# board.net
KiCad netlist of a schematic drawn in EAGLE
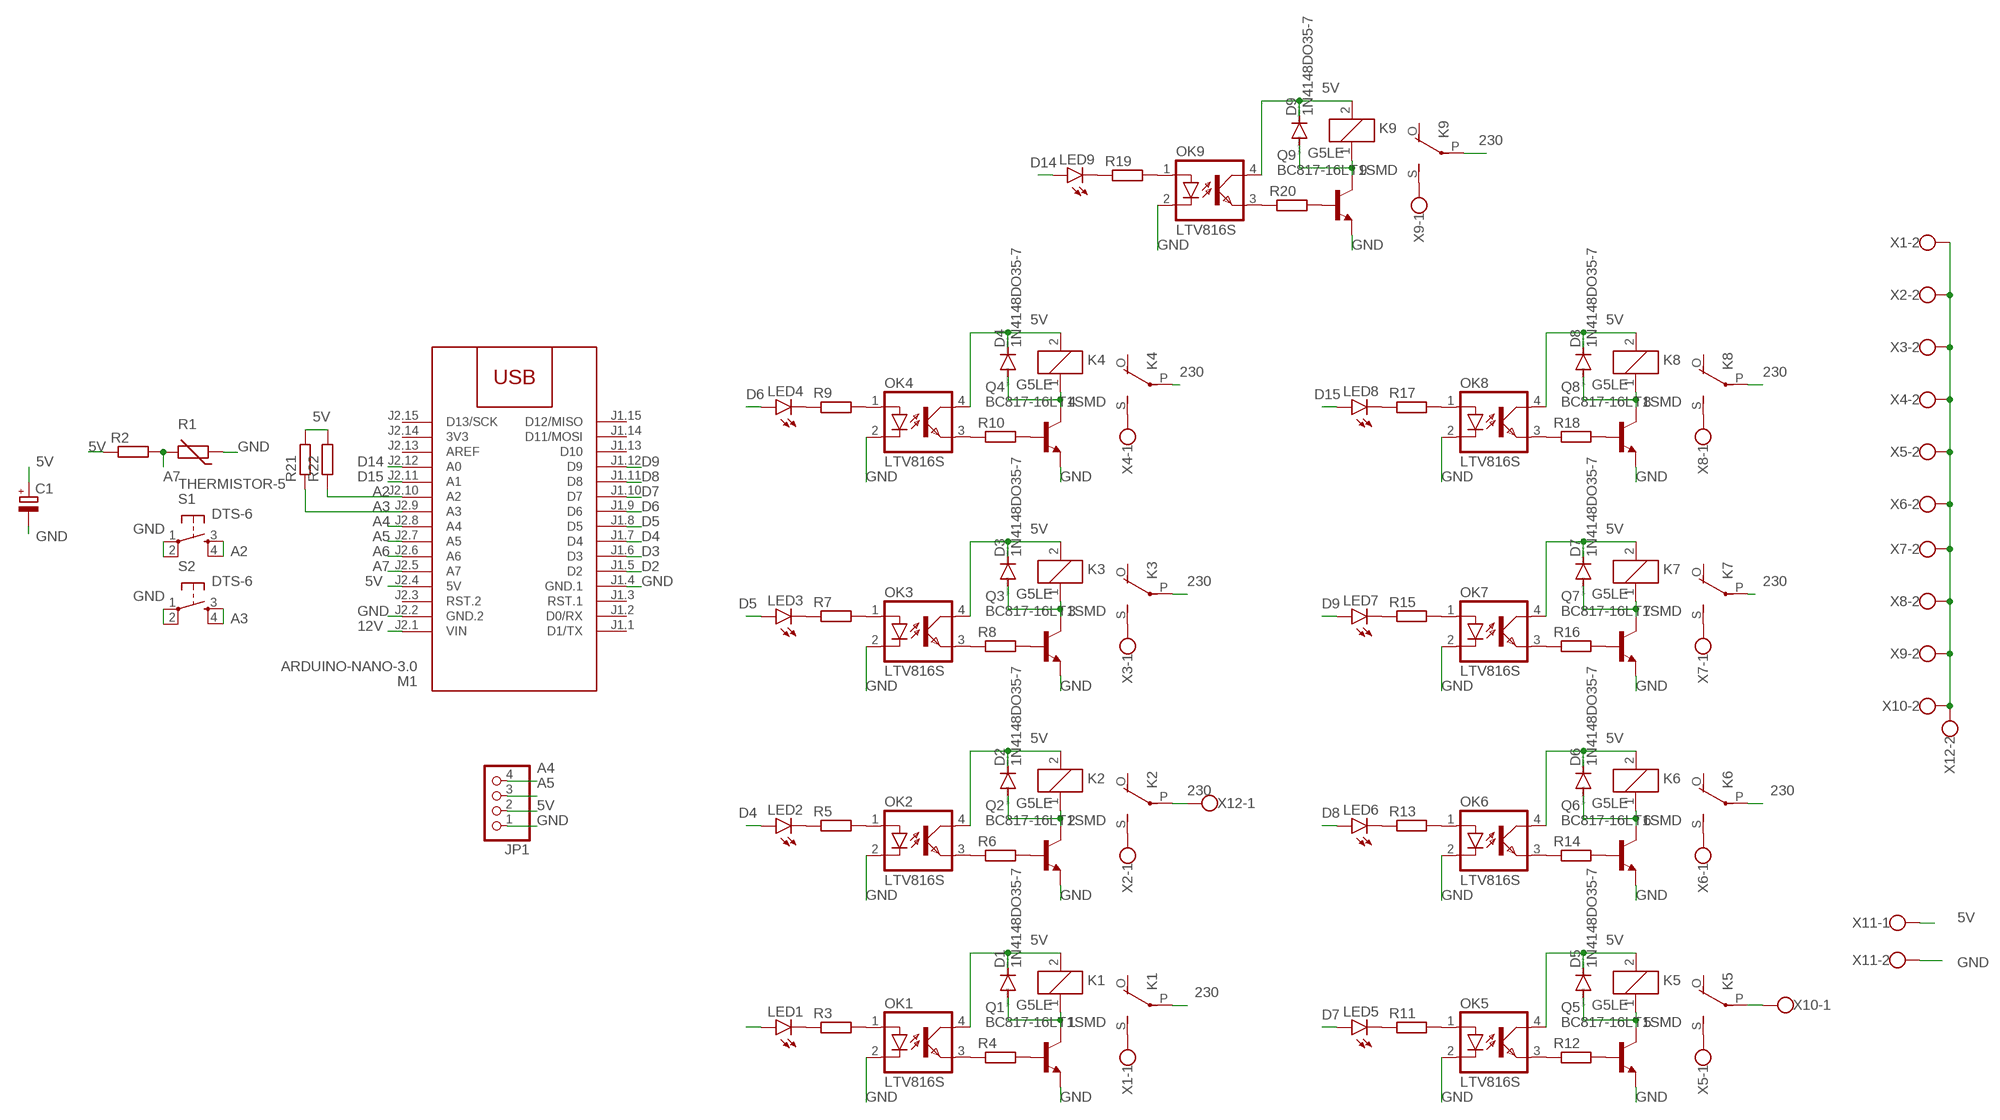
[diagram p0: schematic, sheet 1]

(export (version "E")
  (design (tool "Eeschema 10.0.6"))
  (components
    (comp (ref "C1")
      (value "CPOL-EUB45181A")
      (footprint "eagle-import:B45181A")
      (libsource (lib "eagle-import") (part "CPOL-EUB45181A"))
    )
    (comp (ref "D1")
      (value "1N4148DO35-7")
      (footprint "eagle-import:DO35-7")
      (libsource (lib "eagle-import") (part "1N4148DO35-7"))
    )
    (comp (ref "D2")
      (value "1N4148DO35-7")
      (footprint "eagle-import:DO35-7")
      (libsource (lib "eagle-import") (part "1N4148DO35-7"))
    )
    (comp (ref "D3")
      (value "1N4148DO35-7")
      (footprint "eagle-import:DO35-7")
      (libsource (lib "eagle-import") (part "1N4148DO35-7"))
    )
    (comp (ref "D4")
      (value "1N4148DO35-7")
      (footprint "eagle-import:DO35-7")
      (libsource (lib "eagle-import") (part "1N4148DO35-7"))
    )
    (comp (ref "D5")
      (value "1N4148DO35-7")
      (footprint "eagle-import:DO35-7")
      (libsource (lib "eagle-import") (part "1N4148DO35-7"))
    )
    (comp (ref "D6")
      (value "1N4148DO35-7")
      (footprint "eagle-import:DO35-7")
      (libsource (lib "eagle-import") (part "1N4148DO35-7"))
    )
    (comp (ref "D7")
      (value "1N4148DO35-7")
      (footprint "eagle-import:DO35-7")
      (libsource (lib "eagle-import") (part "1N4148DO35-7"))
    )
    (comp (ref "D8")
      (value "1N4148DO35-7")
      (footprint "eagle-import:DO35-7")
      (libsource (lib "eagle-import") (part "1N4148DO35-7"))
    )
    (comp (ref "D9")
      (value "1N4148DO35-7")
      (footprint "eagle-import:DO35-7")
      (libsource (lib "eagle-import") (part "1N4148DO35-7"))
    )
    (comp (ref "JP1")
      (value "PINHD-1X4")
      (footprint "eagle-import:1X04")
      (libsource (lib "eagle-import") (part "PINHD-1X4"))
    )
    (comp (ref "K1")
      (value "G5LE")
      (footprint "eagle-import:G5LE")
      (libsource (lib "eagle-import") (part "G5LE"))
    )
    (comp (ref "K2")
      (value "G5LE")
      (footprint "eagle-import:G5LE")
      (libsource (lib "eagle-import") (part "G5LE"))
    )
    (comp (ref "K3")
      (value "G5LE")
      (footprint "eagle-import:G5LE")
      (libsource (lib "eagle-import") (part "G5LE"))
    )
    (comp (ref "K4")
      (value "G5LE")
      (footprint "eagle-import:G5LE")
      (libsource (lib "eagle-import") (part "G5LE"))
    )
    (comp (ref "K5")
      (value "G5LE")
      (footprint "eagle-import:G5LE")
      (libsource (lib "eagle-import") (part "G5LE"))
    )
    (comp (ref "K6")
      (value "G5LE")
      (footprint "eagle-import:G5LE")
      (libsource (lib "eagle-import") (part "G5LE"))
    )
    (comp (ref "K7")
      (value "G5LE")
      (footprint "eagle-import:G5LE")
      (libsource (lib "eagle-import") (part "G5LE"))
    )
    (comp (ref "K8")
      (value "G5LE")
      (footprint "eagle-import:G5LE")
      (libsource (lib "eagle-import") (part "G5LE"))
    )
    (comp (ref "K9")
      (value "G5LE")
      (footprint "eagle-import:G5LE")
      (libsource (lib "eagle-import") (part "G5LE"))
    )
    (comp (ref "LED1")
      (value "LED3MM")
      (footprint "eagle-import:LED3MM")
      (libsource (lib "eagle-import") (part "LED3MM"))
    )
    (comp (ref "LED2")
      (value "LED3MM")
      (footprint "eagle-import:LED3MM")
      (libsource (lib "eagle-import") (part "LED3MM"))
    )
    (comp (ref "LED3")
      (value "LED3MM")
      (footprint "eagle-import:LED3MM")
      (libsource (lib "eagle-import") (part "LED3MM"))
    )
    (comp (ref "LED4")
      (value "LED3MM")
      (footprint "eagle-import:LED3MM")
      (libsource (lib "eagle-import") (part "LED3MM"))
    )
    (comp (ref "LED5")
      (value "LED3MM")
      (footprint "eagle-import:LED3MM")
      (libsource (lib "eagle-import") (part "LED3MM"))
    )
    (comp (ref "LED6")
      (value "LED3MM")
      (footprint "eagle-import:LED3MM")
      (libsource (lib "eagle-import") (part "LED3MM"))
    )
    (comp (ref "LED7")
      (value "LED3MM")
      (footprint "eagle-import:LED3MM")
      (libsource (lib "eagle-import") (part "LED3MM"))
    )
    (comp (ref "LED8")
      (value "LED3MM")
      (footprint "eagle-import:LED3MM")
      (libsource (lib "eagle-import") (part "LED3MM"))
    )
    (comp (ref "LED9")
      (value "LED3MM")
      (footprint "eagle-import:LED3MM")
      (libsource (lib "eagle-import") (part "LED3MM"))
    )
    (comp (ref "M1")
      (value "ARDUINO-NANO-3.0")
      (footprint "eagle-import:ARDUINO-NANO-3.0")
      (libsource (lib "eagle-import") (part "ARDUINO-NANO-3.0"))
    )
    (comp (ref "OK1")
      (value "LTV816S")
      (footprint "eagle-import:DIL4-SMD")
      (libsource (lib "eagle-import") (part "LTV816S"))
    )
    (comp (ref "OK2")
      (value "LTV816S")
      (footprint "eagle-import:DIL4-SMD")
      (libsource (lib "eagle-import") (part "LTV816S"))
    )
    (comp (ref "OK3")
      (value "LTV816S")
      (footprint "eagle-import:DIL4-SMD")
      (libsource (lib "eagle-import") (part "LTV816S"))
    )
    (comp (ref "OK4")
      (value "LTV816S")
      (footprint "eagle-import:DIL4-SMD")
      (libsource (lib "eagle-import") (part "LTV816S"))
    )
    (comp (ref "OK5")
      (value "LTV816S")
      (footprint "eagle-import:DIL4-SMD")
      (libsource (lib "eagle-import") (part "LTV816S"))
    )
    (comp (ref "OK6")
      (value "LTV816S")
      (footprint "eagle-import:DIL4-SMD")
      (libsource (lib "eagle-import") (part "LTV816S"))
    )
    (comp (ref "OK7")
      (value "LTV816S")
      (footprint "eagle-import:DIL4-SMD")
      (libsource (lib "eagle-import") (part "LTV816S"))
    )
    (comp (ref "OK8")
      (value "LTV816S")
      (footprint "eagle-import:DIL4-SMD")
      (libsource (lib "eagle-import") (part "LTV816S"))
    )
    (comp (ref "OK9")
      (value "LTV816S")
      (footprint "eagle-import:DIL4-SMD")
      (libsource (lib "eagle-import") (part "LTV816S"))
    )
    (comp (ref "Q1")
      (value "BC817-16LT1SMD")
      (footprint "eagle-import:SOT23-BEC")
      (libsource (lib "eagle-import") (part "BC817SMD-16LT1"))
    )
    (comp (ref "Q2")
      (value "BC817-16LT1SMD")
      (footprint "eagle-import:SOT23-BEC")
      (libsource (lib "eagle-import") (part "BC817SMD-16LT1"))
    )
    (comp (ref "Q3")
      (value "BC817-16LT1SMD")
      (footprint "eagle-import:SOT23-BEC")
      (libsource (lib "eagle-import") (part "BC817SMD-16LT1"))
    )
    (comp (ref "Q4")
      (value "BC817-16LT1SMD")
      (footprint "eagle-import:SOT23-BEC")
      (libsource (lib "eagle-import") (part "BC817SMD-16LT1"))
    )
    (comp (ref "Q5")
      (value "BC817-16LT1SMD")
      (footprint "eagle-import:SOT23-BEC")
      (libsource (lib "eagle-import") (part "BC817SMD-16LT1"))
    )
    (comp (ref "Q6")
      (value "BC817-16LT1SMD")
      (footprint "eagle-import:SOT23-BEC")
      (libsource (lib "eagle-import") (part "BC817SMD-16LT1"))
    )
    (comp (ref "Q7")
      (value "BC817-16LT1SMD")
      (footprint "eagle-import:SOT23-BEC")
      (libsource (lib "eagle-import") (part "BC817SMD-16LT1"))
    )
    (comp (ref "Q8")
      (value "BC817-16LT1SMD")
      (footprint "eagle-import:SOT23-BEC")
      (libsource (lib "eagle-import") (part "BC817SMD-16LT1"))
    )
    (comp (ref "Q9")
      (value "BC817-16LT1SMD")
      (footprint "eagle-import:SOT23-BEC")
      (libsource (lib "eagle-import") (part "BC817SMD-16LT1"))
    )
    (comp (ref "R1")
      (value "THERMISTOR-5")
      (footprint "eagle-import:R-5")
      (libsource (lib "eagle-import") (part "THERMISTOR-5"))
    )
    (comp (ref "R2")
      (value "R-EU_0207/10")
      (footprint "eagle-import:0207_10")
      (libsource (lib "eagle-import") (part "R-EU_0207/10"))
    )
    (comp (ref "R3")
      (value "R-EU_R1206")
      (footprint "eagle-import:R1206")
      (libsource (lib "eagle-import") (part "R-EU_R1206"))
    )
    (comp (ref "R4")
      (value "R-EU_R1206")
      (footprint "eagle-import:R1206")
      (libsource (lib "eagle-import") (part "R-EU_R1206"))
    )
    (comp (ref "R5")
      (value "R-EU_R1206")
      (footprint "eagle-import:R1206")
      (libsource (lib "eagle-import") (part "R-EU_R1206"))
    )
    (comp (ref "R6")
      (value "R-EU_R1206")
      (footprint "eagle-import:R1206")
      (libsource (lib "eagle-import") (part "R-EU_R1206"))
    )
    (comp (ref "R7")
      (value "R-EU_R1206")
      (footprint "eagle-import:R1206")
      (libsource (lib "eagle-import") (part "R-EU_R1206"))
    )
    (comp (ref "R8")
      (value "R-EU_R1206")
      (footprint "eagle-import:R1206")
      (libsource (lib "eagle-import") (part "R-EU_R1206"))
    )
    (comp (ref "R9")
      (value "R-EU_R1206")
      (footprint "eagle-import:R1206")
      (libsource (lib "eagle-import") (part "R-EU_R1206"))
    )
    (comp (ref "R10")
      (value "R-EU_R1206")
      (footprint "eagle-import:R1206")
      (libsource (lib "eagle-import") (part "R-EU_R1206"))
    )
    (comp (ref "R11")
      (value "R-EU_R1206")
      (footprint "eagle-import:R1206")
      (libsource (lib "eagle-import") (part "R-EU_R1206"))
    )
    (comp (ref "R12")
      (value "R-EU_R1206")
      (footprint "eagle-import:R1206")
      (libsource (lib "eagle-import") (part "R-EU_R1206"))
    )
    (comp (ref "R13")
      (value "R-EU_R1206")
      (footprint "eagle-import:R1206")
      (libsource (lib "eagle-import") (part "R-EU_R1206"))
    )
    (comp (ref "R14")
      (value "R-EU_R1206")
      (footprint "eagle-import:R1206")
      (libsource (lib "eagle-import") (part "R-EU_R1206"))
    )
    (comp (ref "R15")
      (value "R-EU_R1206")
      (footprint "eagle-import:R1206")
      (libsource (lib "eagle-import") (part "R-EU_R1206"))
    )
    (comp (ref "R16")
      (value "R-EU_R1206")
      (footprint "eagle-import:R1206")
      (libsource (lib "eagle-import") (part "R-EU_R1206"))
    )
    (comp (ref "R17")
      (value "R-EU_R1206")
      (footprint "eagle-import:R1206")
      (libsource (lib "eagle-import") (part "R-EU_R1206"))
    )
    (comp (ref "R18")
      (value "R-EU_R1206")
      (footprint "eagle-import:R1206")
      (libsource (lib "eagle-import") (part "R-EU_R1206"))
    )
    (comp (ref "R19")
      (value "R-EU_R1206")
      (footprint "eagle-import:R1206")
      (libsource (lib "eagle-import") (part "R-EU_R1206"))
    )
    (comp (ref "R20")
      (value "R-EU_R1206")
      (footprint "eagle-import:R1206")
      (libsource (lib "eagle-import") (part "R-EU_R1206"))
    )
    (comp (ref "R21")
      (value "R-EU_0207/10")
      (footprint "eagle-import:0207_10")
      (libsource (lib "eagle-import") (part "R-EU_0207/10"))
    )
    (comp (ref "R22")
      (value "R-EU_0207/10")
      (footprint "eagle-import:0207_10")
      (libsource (lib "eagle-import") (part "R-EU_0207/10"))
    )
    (comp (ref "S1")
      (value "DTS-6")
      (footprint "eagle-import:DTS-6")
      (libsource (lib "eagle-import") (part "DTS-6"))
    )
    (comp (ref "S2")
      (value "DTS-6")
      (footprint "eagle-import:DTS-6")
      (libsource (lib "eagle-import") (part "DTS-6"))
    )
    (comp (ref "X1")
      (value "W237-102")
      (footprint "eagle-import:W237-102")
      (fields (field (name "MPN") "237-102"))
      (libsource (lib "eagle-import") (part "W237-102"))
    )
    (comp (ref "X2")
      (value "W237-102")
      (footprint "eagle-import:W237-102")
      (fields (field (name "MPN") "237-102"))
      (libsource (lib "eagle-import") (part "W237-102"))
    )
    (comp (ref "X3")
      (value "W237-102")
      (footprint "eagle-import:W237-102")
      (fields (field (name "MPN") "237-102"))
      (libsource (lib "eagle-import") (part "W237-102"))
    )
    (comp (ref "X4")
      (value "W237-102")
      (footprint "eagle-import:W237-102")
      (fields (field (name "MPN") "237-102"))
      (libsource (lib "eagle-import") (part "W237-102"))
    )
    (comp (ref "X5")
      (value "W237-102")
      (footprint "eagle-import:W237-102")
      (fields (field (name "MPN") "237-102"))
      (libsource (lib "eagle-import") (part "W237-102"))
    )
    (comp (ref "X6")
      (value "W237-102")
      (footprint "eagle-import:W237-102")
      (fields (field (name "MPN") "237-102"))
      (libsource (lib "eagle-import") (part "W237-102"))
    )
    (comp (ref "X7")
      (value "W237-102")
      (footprint "eagle-import:W237-102")
      (fields (field (name "MPN") "237-102"))
      (libsource (lib "eagle-import") (part "W237-102"))
    )
    (comp (ref "X8")
      (value "W237-102")
      (footprint "eagle-import:W237-102")
      (fields (field (name "MPN") "237-102"))
      (libsource (lib "eagle-import") (part "W237-102"))
    )
    (comp (ref "X9")
      (value "W237-102")
      (footprint "eagle-import:W237-102")
      (fields (field (name "MPN") "237-102"))
      (libsource (lib "eagle-import") (part "W237-102"))
    )
    (comp (ref "X10")
      (value "W237-102")
      (footprint "eagle-import:W237-102")
      (fields (field (name "MPN") "237-102"))
      (libsource (lib "eagle-import") (part "W237-102"))
    )
    (comp (ref "X11")
      (value "W237-102")
      (footprint "eagle-import:W237-102")
      (fields (field (name "MPN") "237-102"))
      (libsource (lib "eagle-import") (part "W237-102"))
    )
    (comp (ref "X12")
      (value "W237-102")
      (footprint "eagle-import:W237-102")
      (fields (field (name "MPN") "237-102"))
      (libsource (lib "eagle-import") (part "W237-102"))
    )
  )
  (nets
    (net (code "1") (name "/1") (class "Default")
      (node (ref "D1") (pin "A") (pinfunction "A_A") (pintype "passive"))
      (node (ref "K1") (pin "1") (pinfunction "1_1") (pintype "passive"))
      (node (ref "Q1") (pin "C") (pinfunction "C_C") (pintype "passive"))
    )
    (net (code "2") (name "/2") (class "Default")
      (node (ref "D2") (pin "A") (pinfunction "A_A") (pintype "passive"))
      (node (ref "K2") (pin "1") (pinfunction "1_1") (pintype "passive"))
      (node (ref "Q2") (pin "C") (pinfunction "C_C") (pintype "passive"))
    )
    (net (code "3") (name "/3") (class "Default")
      (node (ref "D3") (pin "A") (pinfunction "A_A") (pintype "passive"))
      (node (ref "K3") (pin "1") (pinfunction "1_1") (pintype "passive"))
      (node (ref "Q3") (pin "C") (pinfunction "C_C") (pintype "passive"))
    )
    (net (code "4") (name "/3V3") (class "Default")
      (node (ref "M1") (pin "J2.14") (pinfunction "3V3_J2.14") (pintype "power_in"))
    )
    (net (code "5") (name "/4") (class "Default")
      (node (ref "D4") (pin "A") (pinfunction "A_A") (pintype "passive"))
      (node (ref "K4") (pin "1") (pinfunction "1_1") (pintype "passive"))
      (node (ref "Q4") (pin "C") (pinfunction "C_C") (pintype "passive"))
    )
    (net (code "6") (name "/5") (class "Default")
      (node (ref "D5") (pin "A") (pinfunction "A_A") (pintype "passive"))
      (node (ref "K5") (pin "1") (pinfunction "1_1") (pintype "passive"))
      (node (ref "Q5") (pin "C") (pinfunction "C_C") (pintype "passive"))
    )
    (net (code "7") (name "/5V") (class "Default")
      (node (ref "C1") (pin "+") (pinfunction "+_+") (pintype "passive"))
      (node (ref "D1") (pin "C") (pinfunction "C_C") (pintype "passive"))
      (node (ref "D2") (pin "C") (pinfunction "C_C") (pintype "passive"))
      (node (ref "D3") (pin "C") (pinfunction "C_C") (pintype "passive"))
      (node (ref "D4") (pin "C") (pinfunction "C_C") (pintype "passive"))
      (node (ref "D5") (pin "C") (pinfunction "C_C") (pintype "passive"))
      (node (ref "D6") (pin "C") (pinfunction "C_C") (pintype "passive"))
      (node (ref "D7") (pin "C") (pinfunction "C_C") (pintype "passive"))
      (node (ref "D8") (pin "C") (pinfunction "C_C") (pintype "passive"))
      (node (ref "D9") (pin "C") (pinfunction "C_C") (pintype "passive"))
      (node (ref "JP1") (pin "2") (pinfunction "2_2") (pintype "passive"))
      (node (ref "K1") (pin "2") (pinfunction "2_2") (pintype "passive"))
      (node (ref "K2") (pin "2") (pinfunction "2_2") (pintype "passive"))
      (node (ref "K3") (pin "2") (pinfunction "2_2") (pintype "passive"))
      (node (ref "K4") (pin "2") (pinfunction "2_2") (pintype "passive"))
      (node (ref "K5") (pin "2") (pinfunction "2_2") (pintype "passive"))
      (node (ref "K6") (pin "2") (pinfunction "2_2") (pintype "passive"))
      (node (ref "K7") (pin "2") (pinfunction "2_2") (pintype "passive"))
      (node (ref "K8") (pin "2") (pinfunction "2_2") (pintype "passive"))
      (node (ref "K9") (pin "2") (pinfunction "2_2") (pintype "passive"))
      (node (ref "M1") (pin "J2.4") (pinfunction "5V_J2.4") (pintype "power_in"))
      (node (ref "OK1") (pin "4") (pinfunction "COL_4") (pintype "passive"))
      (node (ref "OK2") (pin "4") (pinfunction "COL_4") (pintype "passive"))
      (node (ref "OK3") (pin "4") (pinfunction "COL_4") (pintype "passive"))
      (node (ref "OK4") (pin "4") (pinfunction "COL_4") (pintype "passive"))
      (node (ref "OK5") (pin "4") (pinfunction "COL_4") (pintype "passive"))
      (node (ref "OK6") (pin "4") (pinfunction "COL_4") (pintype "passive"))
      (node (ref "OK7") (pin "4") (pinfunction "COL_4") (pintype "passive"))
      (node (ref "OK8") (pin "4") (pinfunction "COL_4") (pintype "passive"))
      (node (ref "OK9") (pin "4") (pinfunction "COL_4") (pintype "passive"))
      (node (ref "R2") (pin "1") (pinfunction "1_1") (pintype "passive"))
      (node (ref "R21") (pin "2") (pinfunction "2_2") (pintype "passive"))
      (node (ref "R22") (pin "2") (pinfunction "2_2") (pintype "passive"))
      (node (ref "X11") (pin "1") (pinfunction "KL_1") (pintype "passive"))
    )
    (net (code "8") (name "/6") (class "Default")
      (node (ref "D6") (pin "A") (pinfunction "A_A") (pintype "passive"))
      (node (ref "K6") (pin "1") (pinfunction "1_1") (pintype "passive"))
      (node (ref "Q6") (pin "C") (pinfunction "C_C") (pintype "passive"))
    )
    (net (code "9") (name "/7") (class "Default")
      (node (ref "D7") (pin "A") (pinfunction "A_A") (pintype "passive"))
      (node (ref "K7") (pin "1") (pinfunction "1_1") (pintype "passive"))
      (node (ref "Q7") (pin "C") (pinfunction "C_C") (pintype "passive"))
    )
    (net (code "10") (name "/8") (class "Default")
      (node (ref "D8") (pin "A") (pinfunction "A_A") (pintype "passive"))
      (node (ref "K8") (pin "1") (pinfunction "1_1") (pintype "passive"))
      (node (ref "Q8") (pin "C") (pinfunction "C_C") (pintype "passive"))
    )
    (net (code "11") (name "/9") (class "Default")
      (node (ref "D9") (pin "A") (pinfunction "A_A") (pintype "passive"))
      (node (ref "K9") (pin "1") (pinfunction "1_1") (pintype "passive"))
      (node (ref "Q9") (pin "C") (pinfunction "C_C") (pintype "passive"))
    )
    (net (code "12") (name "/12V") (class "Default")
      (node (ref "M1") (pin "J2.1") (pinfunction "VIN_J2.1") (pintype "power_in"))
    )
    (net (code "13") (name "/230") (class "Default")
      (node (ref "K1") (pin "P") (pinfunction "P_P") (pintype "passive"))
      (node (ref "K2") (pin "P") (pinfunction "P_P") (pintype "passive"))
      (node (ref "K3") (pin "P") (pinfunction "P_P") (pintype "passive"))
      (node (ref "K4") (pin "P") (pinfunction "P_P") (pintype "passive"))
      (node (ref "K5") (pin "P") (pinfunction "P_P") (pintype "passive"))
      (node (ref "K6") (pin "P") (pinfunction "P_P") (pintype "passive"))
      (node (ref "K7") (pin "P") (pinfunction "P_P") (pintype "passive"))
      (node (ref "K8") (pin "P") (pinfunction "P_P") (pintype "passive"))
      (node (ref "K9") (pin "P") (pinfunction "P_P") (pintype "passive"))
      (node (ref "X10") (pin "1") (pinfunction "KL_1") (pintype "passive"))
      (node (ref "X12") (pin "1") (pinfunction "KL_1") (pintype "passive"))
    )
    (net (code "14") (name "/A2") (class "Default")
      (node (ref "M1") (pin "J2.10") (pinfunction "A2_J2.10") (pintype "bidirectional"))
      (node (ref "R22") (pin "1") (pinfunction "1_1") (pintype "passive"))
      (node (ref "S1") (pin "3") (pinfunction "3_3") (pintype "passive"))
      (node (ref "S1") (pin "4") (pinfunction "4_4") (pintype "passive"))
    )
    (net (code "15") (name "/A3") (class "Default")
      (node (ref "M1") (pin "J2.9") (pinfunction "A3_J2.9") (pintype "bidirectional"))
      (node (ref "R21") (pin "1") (pinfunction "1_1") (pintype "passive"))
      (node (ref "S2") (pin "3") (pinfunction "3_3") (pintype "passive"))
      (node (ref "S2") (pin "4") (pinfunction "4_4") (pintype "passive"))
    )
    (net (code "16") (name "/A4") (class "Default")
      (node (ref "JP1") (pin "4") (pinfunction "4_4") (pintype "passive"))
      (node (ref "M1") (pin "J2.8") (pinfunction "A4_J2.8") (pintype "bidirectional"))
    )
    (net (code "17") (name "/A5") (class "Default")
      (node (ref "JP1") (pin "3") (pinfunction "3_3") (pintype "passive"))
      (node (ref "M1") (pin "J2.7") (pinfunction "A5_J2.7") (pintype "bidirectional"))
    )
    (net (code "18") (name "/A6") (class "Default")
      (node (ref "M1") (pin "J2.6") (pinfunction "A6_J2.6") (pintype "bidirectional"))
    )
    (net (code "19") (name "/A7") (class "Default")
      (node (ref "M1") (pin "J2.5") (pinfunction "A7_J2.5") (pintype "bidirectional"))
      (node (ref "R1") (pin "2") (pinfunction "2_2") (pintype "passive"))
      (node (ref "R2") (pin "2") (pinfunction "2_2") (pintype "passive"))
    )
    (net (code "20") (name "/D2") (class "Default")
      (node (ref "M1") (pin "J1.5") (pinfunction "D2_J1.5") (pintype "bidirectional"))
    )
    (net (code "21") (name "/D3") (class "Default")
      (node (ref "LED1") (pin "A") (pinfunction "A_A") (pintype "passive"))
      (node (ref "M1") (pin "J1.6") (pinfunction "D3_J1.6") (pintype "bidirectional"))
    )
    (net (code "22") (name "/D4") (class "Default")
      (node (ref "LED2") (pin "A") (pinfunction "A_A") (pintype "passive"))
      (node (ref "M1") (pin "J1.7") (pinfunction "D4_J1.7") (pintype "bidirectional"))
    )
    (net (code "23") (name "/D5") (class "Default")
      (node (ref "LED3") (pin "A") (pinfunction "A_A") (pintype "passive"))
      (node (ref "M1") (pin "J1.8") (pinfunction "D5_J1.8") (pintype "bidirectional"))
    )
    (net (code "24") (name "/D6") (class "Default")
      (node (ref "LED4") (pin "A") (pinfunction "A_A") (pintype "passive"))
      (node (ref "M1") (pin "J1.9") (pinfunction "D6_J1.9") (pintype "bidirectional"))
    )
    (net (code "25") (name "/D7") (class "Default")
      (node (ref "LED5") (pin "A") (pinfunction "A_A") (pintype "passive"))
      (node (ref "M1") (pin "J1.10") (pinfunction "D7_J1.10") (pintype "bidirectional"))
    )
    (net (code "26") (name "/D8") (class "Default")
      (node (ref "LED6") (pin "A") (pinfunction "A_A") (pintype "passive"))
      (node (ref "M1") (pin "J1.11") (pinfunction "D8_J1.11") (pintype "bidirectional"))
    )
    (net (code "27") (name "/D9") (class "Default")
      (node (ref "LED7") (pin "A") (pinfunction "A_A") (pintype "passive"))
      (node (ref "M1") (pin "J1.12") (pinfunction "D9_J1.12") (pintype "bidirectional"))
    )
    (net (code "28") (name "/D14") (class "Default")
      (node (ref "LED9") (pin "A") (pinfunction "A_A") (pintype "passive"))
      (node (ref "M1") (pin "J2.12") (pinfunction "A0_J2.12") (pintype "bidirectional"))
    )
    (net (code "29") (name "/D15") (class "Default")
      (node (ref "LED8") (pin "A") (pinfunction "A_A") (pintype "passive"))
      (node (ref "M1") (pin "J2.11") (pinfunction "A1_J2.11") (pintype "bidirectional"))
    )
    (net (code "30") (name "/GND") (class "Default")
      (node (ref "C1") (pin "-") (pinfunction "-_-") (pintype "passive"))
      (node (ref "JP1") (pin "1") (pinfunction "1_1") (pintype "passive"))
      (node (ref "M1") (pin "J1.4") (pinfunction "GND.1_J1.4") (pintype "power_in"))
      (node (ref "M1") (pin "J2.2") (pinfunction "GND.2_J2.2") (pintype "power_in"))
      (node (ref "OK1") (pin "2") (pinfunction "C_2") (pintype "passive"))
      (node (ref "OK2") (pin "2") (pinfunction "C_2") (pintype "passive"))
      (node (ref "OK3") (pin "2") (pinfunction "C_2") (pintype "passive"))
      (node (ref "OK4") (pin "2") (pinfunction "C_2") (pintype "passive"))
      (node (ref "OK5") (pin "2") (pinfunction "C_2") (pintype "passive"))
      (node (ref "OK6") (pin "2") (pinfunction "C_2") (pintype "passive"))
      (node (ref "OK7") (pin "2") (pinfunction "C_2") (pintype "passive"))
      (node (ref "OK8") (pin "2") (pinfunction "C_2") (pintype "passive"))
      (node (ref "OK9") (pin "2") (pinfunction "C_2") (pintype "passive"))
      (node (ref "Q1") (pin "E") (pinfunction "E_E") (pintype "passive"))
      (node (ref "Q2") (pin "E") (pinfunction "E_E") (pintype "passive"))
      (node (ref "Q3") (pin "E") (pinfunction "E_E") (pintype "passive"))
      (node (ref "Q4") (pin "E") (pinfunction "E_E") (pintype "passive"))
      (node (ref "Q5") (pin "E") (pinfunction "E_E") (pintype "passive"))
      (node (ref "Q6") (pin "E") (pinfunction "E_E") (pintype "passive"))
      (node (ref "Q7") (pin "E") (pinfunction "E_E") (pintype "passive"))
      (node (ref "Q8") (pin "E") (pinfunction "E_E") (pintype "passive"))
      (node (ref "Q9") (pin "E") (pinfunction "E_E") (pintype "passive"))
      (node (ref "R1") (pin "1") (pinfunction "1_1") (pintype "passive"))
      (node (ref "S1") (pin "1") (pinfunction "1_1") (pintype "passive"))
      (node (ref "S1") (pin "2") (pinfunction "2_2") (pintype "passive"))
      (node (ref "S2") (pin "1") (pinfunction "1_1") (pintype "passive"))
      (node (ref "S2") (pin "2") (pinfunction "2_2") (pintype "passive"))
      (node (ref "X11") (pin "2") (pinfunction "KL_2") (pintype "passive"))
    )
    (net (code "31") (name "Net-(LED1-C)") (class "Default")
      (node (ref "LED1") (pin "K") (pinfunction "C_K") (pintype "passive"))
      (node (ref "R3") (pin "1") (pinfunction "1_1") (pintype "passive"))
    )
    (net (code "32") (name "Net-(LED2-C)") (class "Default")
      (node (ref "LED2") (pin "K") (pinfunction "C_K") (pintype "passive"))
      (node (ref "R5") (pin "1") (pinfunction "1_1") (pintype "passive"))
    )
    (net (code "33") (name "Net-(LED3-C)") (class "Default")
      (node (ref "LED3") (pin "K") (pinfunction "C_K") (pintype "passive"))
      (node (ref "R7") (pin "1") (pinfunction "1_1") (pintype "passive"))
    )
    (net (code "34") (name "Net-(LED4-C)") (class "Default")
      (node (ref "LED4") (pin "K") (pinfunction "C_K") (pintype "passive"))
      (node (ref "R9") (pin "1") (pinfunction "1_1") (pintype "passive"))
    )
    (net (code "35") (name "Net-(LED5-C)") (class "Default")
      (node (ref "LED5") (pin "K") (pinfunction "C_K") (pintype "passive"))
      (node (ref "R11") (pin "1") (pinfunction "1_1") (pintype "passive"))
    )
    (net (code "36") (name "Net-(LED6-C)") (class "Default")
      (node (ref "LED6") (pin "K") (pinfunction "C_K") (pintype "passive"))
      (node (ref "R13") (pin "1") (pinfunction "1_1") (pintype "passive"))
    )
    (net (code "37") (name "Net-(LED7-C)") (class "Default")
      (node (ref "LED7") (pin "K") (pinfunction "C_K") (pintype "passive"))
      (node (ref "R15") (pin "1") (pinfunction "1_1") (pintype "passive"))
    )
    (net (code "38") (name "Net-(LED8-C)") (class "Default")
      (node (ref "LED8") (pin "K") (pinfunction "C_K") (pintype "passive"))
      (node (ref "R17") (pin "1") (pinfunction "1_1") (pintype "passive"))
    )
    (net (code "39") (name "Net-(LED9-C)") (class "Default")
      (node (ref "LED9") (pin "K") (pinfunction "C_K") (pintype "passive"))
      (node (ref "R19") (pin "1") (pinfunction "1_1") (pintype "passive"))
    )
    (net (code "40") (name "Net-(OK1-A)") (class "Default")
      (node (ref "OK1") (pin "1") (pinfunction "A_1") (pintype "passive"))
      (node (ref "R3") (pin "2") (pinfunction "2_2") (pintype "passive"))
    )
    (net (code "41") (name "Net-(OK1-EMIT)") (class "Default")
      (node (ref "OK1") (pin "3") (pinfunction "EMIT_3") (pintype "passive"))
      (node (ref "R4") (pin "1") (pinfunction "1_1") (pintype "passive"))
    )
    (net (code "42") (name "Net-(OK2-A)") (class "Default")
      (node (ref "OK2") (pin "1") (pinfunction "A_1") (pintype "passive"))
      (node (ref "R5") (pin "2") (pinfunction "2_2") (pintype "passive"))
    )
    (net (code "43") (name "Net-(OK2-EMIT)") (class "Default")
      (node (ref "OK2") (pin "3") (pinfunction "EMIT_3") (pintype "passive"))
      (node (ref "R6") (pin "1") (pinfunction "1_1") (pintype "passive"))
    )
    (net (code "44") (name "Net-(OK3-A)") (class "Default")
      (node (ref "OK3") (pin "1") (pinfunction "A_1") (pintype "passive"))
      (node (ref "R7") (pin "2") (pinfunction "2_2") (pintype "passive"))
    )
    (net (code "45") (name "Net-(OK3-EMIT)") (class "Default")
      (node (ref "OK3") (pin "3") (pinfunction "EMIT_3") (pintype "passive"))
      (node (ref "R8") (pin "1") (pinfunction "1_1") (pintype "passive"))
    )
    (net (code "46") (name "Net-(OK4-A)") (class "Default")
      (node (ref "OK4") (pin "1") (pinfunction "A_1") (pintype "passive"))
      (node (ref "R9") (pin "2") (pinfunction "2_2") (pintype "passive"))
    )
    (net (code "47") (name "Net-(OK4-EMIT)") (class "Default")
      (node (ref "OK4") (pin "3") (pinfunction "EMIT_3") (pintype "passive"))
      (node (ref "R10") (pin "1") (pinfunction "1_1") (pintype "passive"))
    )
    (net (code "48") (name "Net-(OK5-A)") (class "Default")
      (node (ref "OK5") (pin "1") (pinfunction "A_1") (pintype "passive"))
      (node (ref "R11") (pin "2") (pinfunction "2_2") (pintype "passive"))
    )
    (net (code "49") (name "Net-(OK5-EMIT)") (class "Default")
      (node (ref "OK5") (pin "3") (pinfunction "EMIT_3") (pintype "passive"))
      (node (ref "R12") (pin "1") (pinfunction "1_1") (pintype "passive"))
    )
    (net (code "50") (name "Net-(OK6-A)") (class "Default")
      (node (ref "OK6") (pin "1") (pinfunction "A_1") (pintype "passive"))
      (node (ref "R13") (pin "2") (pinfunction "2_2") (pintype "passive"))
    )
    (net (code "51") (name "Net-(OK6-EMIT)") (class "Default")
      (node (ref "OK6") (pin "3") (pinfunction "EMIT_3") (pintype "passive"))
      (node (ref "R14") (pin "1") (pinfunction "1_1") (pintype "passive"))
    )
    (net (code "52") (name "Net-(OK7-A)") (class "Default")
      (node (ref "OK7") (pin "1") (pinfunction "A_1") (pintype "passive"))
      (node (ref "R15") (pin "2") (pinfunction "2_2") (pintype "passive"))
    )
    (net (code "53") (name "Net-(OK7-EMIT)") (class "Default")
      (node (ref "OK7") (pin "3") (pinfunction "EMIT_3") (pintype "passive"))
      (node (ref "R16") (pin "1") (pinfunction "1_1") (pintype "passive"))
    )
    (net (code "54") (name "Net-(OK8-A)") (class "Default")
      (node (ref "OK8") (pin "1") (pinfunction "A_1") (pintype "passive"))
      (node (ref "R17") (pin "2") (pinfunction "2_2") (pintype "passive"))
    )
    (net (code "55") (name "Net-(OK8-EMIT)") (class "Default")
      (node (ref "OK8") (pin "3") (pinfunction "EMIT_3") (pintype "passive"))
      (node (ref "R18") (pin "1") (pinfunction "1_1") (pintype "passive"))
    )
    (net (code "56") (name "Net-(OK9-A)") (class "Default")
      (node (ref "OK9") (pin "1") (pinfunction "A_1") (pintype "passive"))
      (node (ref "R19") (pin "2") (pinfunction "2_2") (pintype "passive"))
    )
    (net (code "57") (name "Net-(OK9-EMIT)") (class "Default")
      (node (ref "OK9") (pin "3") (pinfunction "EMIT_3") (pintype "passive"))
      (node (ref "R20") (pin "1") (pinfunction "1_1") (pintype "passive"))
    )
    (net (code "58") (name "Net-(Q1-PadB)") (class "Default")
      (node (ref "Q1") (pin "B") (pinfunction "B_B") (pintype "passive"))
      (node (ref "R4") (pin "2") (pinfunction "2_2") (pintype "passive"))
    )
    (net (code "59") (name "Net-(Q2-PadB)") (class "Default")
      (node (ref "Q2") (pin "B") (pinfunction "B_B") (pintype "passive"))
      (node (ref "R6") (pin "2") (pinfunction "2_2") (pintype "passive"))
    )
    (net (code "60") (name "Net-(Q3-PadB)") (class "Default")
      (node (ref "Q3") (pin "B") (pinfunction "B_B") (pintype "passive"))
      (node (ref "R8") (pin "2") (pinfunction "2_2") (pintype "passive"))
    )
    (net (code "61") (name "Net-(Q4-PadB)") (class "Default")
      (node (ref "Q4") (pin "B") (pinfunction "B_B") (pintype "passive"))
      (node (ref "R10") (pin "2") (pinfunction "2_2") (pintype "passive"))
    )
    (net (code "62") (name "Net-(Q5-PadB)") (class "Default")
      (node (ref "Q5") (pin "B") (pinfunction "B_B") (pintype "passive"))
      (node (ref "R12") (pin "2") (pinfunction "2_2") (pintype "passive"))
    )
    (net (code "63") (name "Net-(Q6-PadB)") (class "Default")
      (node (ref "Q6") (pin "B") (pinfunction "B_B") (pintype "passive"))
      (node (ref "R14") (pin "2") (pinfunction "2_2") (pintype "passive"))
    )
    (net (code "64") (name "Net-(Q7-PadB)") (class "Default")
      (node (ref "Q7") (pin "B") (pinfunction "B_B") (pintype "passive"))
      (node (ref "R16") (pin "2") (pinfunction "2_2") (pintype "passive"))
    )
    (net (code "65") (name "Net-(Q8-PadB)") (class "Default")
      (node (ref "Q8") (pin "B") (pinfunction "B_B") (pintype "passive"))
      (node (ref "R18") (pin "2") (pinfunction "2_2") (pintype "passive"))
    )
    (net (code "66") (name "Net-(Q9-PadB)") (class "Default")
      (node (ref "Q9") (pin "B") (pinfunction "B_B") (pintype "passive"))
      (node (ref "R20") (pin "2") (pinfunction "2_2") (pintype "passive"))
    )
    (net (code "67") (name "Net-(X1A-KL)") (class "Default")
      (node (ref "K1") (pin "S") (pinfunction "S_S") (pintype "passive"))
      (node (ref "X1") (pin "1") (pinfunction "KL_1") (pintype "passive"))
    )
    (net (code "68") (name "Net-(X2A-KL)") (class "Default")
      (node (ref "K2") (pin "S") (pinfunction "S_S") (pintype "passive"))
      (node (ref "X2") (pin "1") (pinfunction "KL_1") (pintype "passive"))
    )
    (net (code "69") (name "Net-(X3A-KL)") (class "Default")
      (node (ref "K3") (pin "S") (pinfunction "S_S") (pintype "passive"))
      (node (ref "X3") (pin "1") (pinfunction "KL_1") (pintype "passive"))
    )
    (net (code "70") (name "Net-(X4A-KL)") (class "Default")
      (node (ref "K4") (pin "S") (pinfunction "S_S") (pintype "passive"))
      (node (ref "X4") (pin "1") (pinfunction "KL_1") (pintype "passive"))
    )
    (net (code "71") (name "Net-(X5A-KL)") (class "Default")
      (node (ref "K5") (pin "S") (pinfunction "S_S") (pintype "passive"))
      (node (ref "X5") (pin "1") (pinfunction "KL_1") (pintype "passive"))
    )
    (net (code "72") (name "Net-(X6A-KL)") (class "Default")
      (node (ref "K6") (pin "S") (pinfunction "S_S") (pintype "passive"))
      (node (ref "X6") (pin "1") (pinfunction "KL_1") (pintype "passive"))
    )
    (net (code "73") (name "Net-(X7A-KL)") (class "Default")
      (node (ref "K7") (pin "S") (pinfunction "S_S") (pintype "passive"))
      (node (ref "X7") (pin "1") (pinfunction "KL_1") (pintype "passive"))
    )
    (net (code "74") (name "Net-(X8A-KL)") (class "Default")
      (node (ref "K8") (pin "S") (pinfunction "S_S") (pintype "passive"))
      (node (ref "X8") (pin "1") (pinfunction "KL_1") (pintype "passive"))
    )
    (net (code "75") (name "Net-(X9A-KL)") (class "Default")
      (node (ref "K9") (pin "S") (pinfunction "S_S") (pintype "passive"))
      (node (ref "X9") (pin "1") (pinfunction "KL_1") (pintype "passive"))
    )
    (net (code "76") (name "Net-(X10B-KL)") (class "Default")
      (node (ref "X1") (pin "2") (pinfunction "KL_2") (pintype "passive"))
      (node (ref "X10") (pin "2") (pinfunction "KL_2") (pintype "passive"))
      (node (ref "X12") (pin "2") (pinfunction "KL_2") (pintype "passive"))
      (node (ref "X2") (pin "2") (pinfunction "KL_2") (pintype "passive"))
      (node (ref "X3") (pin "2") (pinfunction "KL_2") (pintype "passive"))
      (node (ref "X4") (pin "2") (pinfunction "KL_2") (pintype "passive"))
      (node (ref "X5") (pin "2") (pinfunction "KL_2") (pintype "passive"))
      (node (ref "X6") (pin "2") (pinfunction "KL_2") (pintype "passive"))
      (node (ref "X7") (pin "2") (pinfunction "KL_2") (pintype "passive"))
      (node (ref "X8") (pin "2") (pinfunction "KL_2") (pintype "passive"))
      (node (ref "X9") (pin "2") (pinfunction "KL_2") (pintype "passive"))
    )
    (net (code "77") (name "unconnected-(K1-PadO)") (class "Default")
      (node (ref "K1") (pin "O") (pinfunction "O_O") (pintype "passive"))
    )
    (net (code "78") (name "unconnected-(K2-PadO)") (class "Default")
      (node (ref "K2") (pin "O") (pinfunction "O_O") (pintype "passive"))
    )
    (net (code "79") (name "unconnected-(K3-PadO)") (class "Default")
      (node (ref "K3") (pin "O") (pinfunction "O_O") (pintype "passive"))
    )
    (net (code "80") (name "unconnected-(K4-PadO)") (class "Default")
      (node (ref "K4") (pin "O") (pinfunction "O_O") (pintype "passive"))
    )
    (net (code "81") (name "unconnected-(K5-PadO)") (class "Default")
      (node (ref "K5") (pin "O") (pinfunction "O_O") (pintype "passive"))
    )
    (net (code "82") (name "unconnected-(K6-PadO)") (class "Default")
      (node (ref "K6") (pin "O") (pinfunction "O_O") (pintype "passive"))
    )
    (net (code "83") (name "unconnected-(K7-PadO)") (class "Default")
      (node (ref "K7") (pin "O") (pinfunction "O_O") (pintype "passive"))
    )
    (net (code "84") (name "unconnected-(K8-PadO)") (class "Default")
      (node (ref "K8") (pin "O") (pinfunction "O_O") (pintype "passive"))
    )
    (net (code "85") (name "unconnected-(K9-PadO)") (class "Default")
      (node (ref "K9") (pin "O") (pinfunction "O_O") (pintype "passive"))
    )
    (net (code "86") (name "unconnected-(M1-AREF-PadJ2.13)") (class "Default")
      (node (ref "M1") (pin "J2.13") (pinfunction "AREF_J2.13") (pintype "bidirectional"))
    )
    (net (code "87") (name "unconnected-(M1-D0{slash}RX-PadJ1.2)") (class "Default")
      (node (ref "M1") (pin "J1.2") (pinfunction "D0/RX_J1.2") (pintype "bidirectional"))
    )
    (net (code "88") (name "unconnected-(M1-D1{slash}TX-PadJ1.1)") (class "Default")
      (node (ref "M1") (pin "J1.1") (pinfunction "D1/TX_J1.1") (pintype "bidirectional"))
    )
    (net (code "89") (name "unconnected-(M1-D10-PadJ1.13)") (class "Default")
      (node (ref "M1") (pin "J1.13") (pinfunction "D10_J1.13") (pintype "bidirectional"))
    )
    (net (code "90") (name "unconnected-(M1-D11{slash}MOSI-PadJ1.14)") (class "Default")
      (node (ref "M1") (pin "J1.14") (pinfunction "D11/MOSI_J1.14") (pintype "bidirectional"))
    )
    (net (code "91") (name "unconnected-(M1-D12{slash}MISO-PadJ1.15)") (class "Default")
      (node (ref "M1") (pin "J1.15") (pinfunction "D12/MISO_J1.15") (pintype "bidirectional"))
    )
    (net (code "92") (name "unconnected-(M1-D13{slash}SCK-PadJ2.15)") (class "Default")
      (node (ref "M1") (pin "J2.15") (pinfunction "D13/SCK_J2.15") (pintype "bidirectional"))
    )
    (net (code "93") (name "unconnected-(M1-RST.1-PadJ1.3)") (class "Default")
      (node (ref "M1") (pin "J1.3") (pinfunction "RST.1_J1.3") (pintype "bidirectional"))
    )
    (net (code "94") (name "unconnected-(M1-RST.2-PadJ2.3)") (class "Default")
      (node (ref "M1") (pin "J2.3") (pinfunction "RST.2_J2.3") (pintype "bidirectional"))
    )
  )
)
